# dualpowersupply.net
KiCad netlist of a schematic drawn in EAGLE
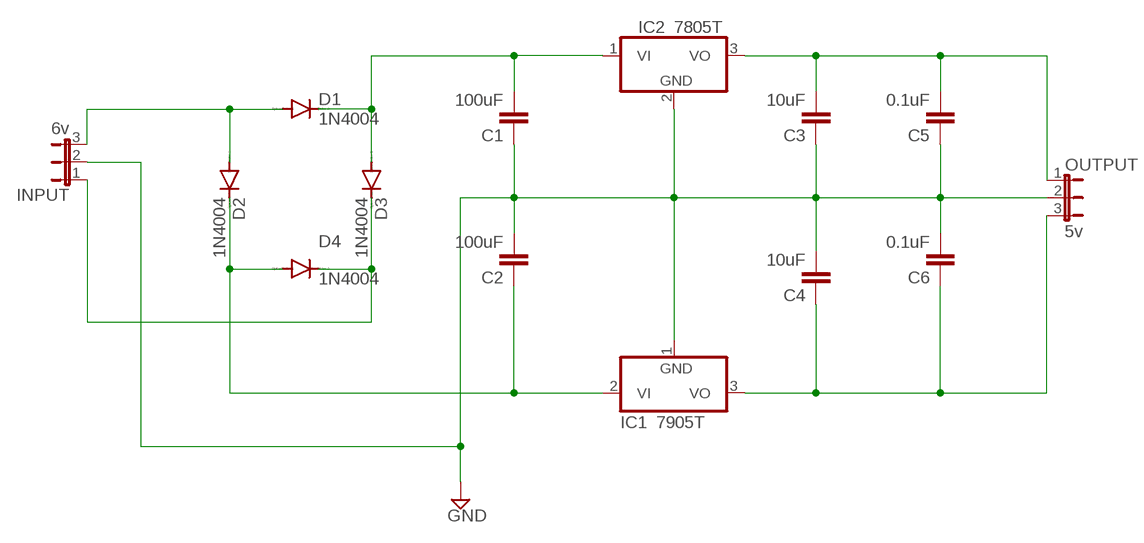
[diagram p0: schematic, sheet 1]

(export (version "E")
  (design (tool "Eeschema 10.0.6"))
  (components
    (comp (ref "C1")
      (value "100uF")
      (footprint "eagle-import:C2.5-2")
      (libsource (lib "eagle-import") (part "C2.5/2"))
    )
    (comp (ref "C2")
      (value "100uF")
      (footprint "eagle-import:C2.5-2")
      (libsource (lib "eagle-import") (part "C2.5/2"))
    )
    (comp (ref "C3")
      (value "10uF")
      (footprint "eagle-import:C2.5-2")
      (libsource (lib "eagle-import") (part "C2.5/2"))
    )
    (comp (ref "C4")
      (value "10uF")
      (footprint "eagle-import:C2.5-2")
      (libsource (lib "eagle-import") (part "C2.5/2"))
    )
    (comp (ref "C5")
      (value "0.1uF")
      (footprint "eagle-import:C2.5-2")
      (libsource (lib "eagle-import") (part "C2.5/2"))
    )
    (comp (ref "C6")
      (value "0.1uF")
      (footprint "eagle-import:C2.5-2")
      (libsource (lib "eagle-import") (part "C2.5/2"))
    )
    (comp (ref "D1")
      (value "1N4004")
      (footprint "eagle-import:DO41-10")
      (libsource (lib "eagle-import") (part "1N4004"))
    )
    (comp (ref "D2")
      (value "1N4004")
      (footprint "eagle-import:DO41-10")
      (libsource (lib "eagle-import") (part "1N4004"))
    )
    (comp (ref "D3")
      (value "1N4004")
      (footprint "eagle-import:DO41-10")
      (libsource (lib "eagle-import") (part "1N4004"))
    )
    (comp (ref "D4")
      (value "1N4004")
      (footprint "eagle-import:DO41-10")
      (libsource (lib "eagle-import") (part "1N4004"))
    )
    (comp (ref "IC1")
      (value "7905T")
      (footprint "eagle-import:TO220H")
      (libsource (lib "eagle-import") (part "79T08"))
    )
    (comp (ref "IC2")
      (value "7805T")
      (footprint "eagle-import:TO220H")
      (libsource (lib "eagle-import") (part "78T05"))
    )
    (comp (ref "INPUT")
      (value "6v")
      (footprint "eagle-import:JP2")
      (libsource (lib "eagle-import") (part "JP2E"))
    )
    (comp (ref "OUTPUT")
      (value "5v")
      (footprint "eagle-import:JP2")
      (libsource (lib "eagle-import") (part "JP2E"))
    )
  )
  (nets
    (net (code "1") (name "GND") (class "Default")
      (node (ref "C1") (pin "1") (pinfunction "1_1") (pintype "passive"))
      (node (ref "C2") (pin "2") (pinfunction "2_2") (pintype "passive"))
      (node (ref "C3") (pin "1") (pinfunction "1_1") (pintype "passive"))
      (node (ref "C4") (pin "2") (pinfunction "2_2") (pintype "passive"))
      (node (ref "C5") (pin "1") (pinfunction "1_1") (pintype "passive"))
      (node (ref "C6") (pin "2") (pinfunction "2_2") (pintype "passive"))
      (node (ref "IC1") (pin "1") (pinfunction "GND_1") (pintype "passive"))
      (node (ref "IC2") (pin "2") (pinfunction "GND_2") (pintype "passive"))
      (node (ref "INPUT") (pin "2") (pinfunction "2_2") (pintype "passive"))
      (node (ref "OUTPUT") (pin "2") (pinfunction "2_2") (pintype "passive"))
    )
    (net (code "2") (name "Net-(D1-PadA)") (class "Default")
      (node (ref "D1") (pin "A") (pinfunction "A_A") (pintype "passive"))
      (node (ref "D2") (pin "A") (pinfunction "A_A") (pintype "passive"))
      (node (ref "INPUT") (pin "3") (pinfunction "3_3") (pintype "passive"))
    )
    (net (code "3") (name "Net-(D3-PadC)") (class "Default")
      (node (ref "D3") (pin "C") (pinfunction "C_C") (pintype "passive"))
      (node (ref "D4") (pin "C") (pinfunction "C_C") (pintype "passive"))
      (node (ref "INPUT") (pin "1") (pinfunction "1_1") (pintype "passive"))
    )
    (net (code "4") (name "Net-(IC1-VI)") (class "Default")
      (node (ref "C2") (pin "1") (pinfunction "1_1") (pintype "passive"))
      (node (ref "D2") (pin "C") (pinfunction "C_C") (pintype "passive"))
      (node (ref "D4") (pin "A") (pinfunction "A_A") (pintype "passive"))
      (node (ref "IC1") (pin "2") (pinfunction "VI_2") (pintype "input"))
    )
    (net (code "5") (name "Net-(IC1-VO)") (class "Default")
      (node (ref "C4") (pin "1") (pinfunction "1_1") (pintype "passive"))
      (node (ref "C6") (pin "1") (pinfunction "1_1") (pintype "passive"))
      (node (ref "IC1") (pin "3") (pinfunction "VO_3") (pintype "passive"))
      (node (ref "OUTPUT") (pin "3") (pinfunction "3_3") (pintype "passive"))
    )
    (net (code "6") (name "Net-(IC2-VI)") (class "Default")
      (node (ref "C1") (pin "2") (pinfunction "2_2") (pintype "passive"))
      (node (ref "D1") (pin "C") (pinfunction "C_C") (pintype "passive"))
      (node (ref "D3") (pin "A") (pinfunction "A_A") (pintype "passive"))
      (node (ref "IC2") (pin "1") (pinfunction "VI_1") (pintype "input"))
    )
    (net (code "7") (name "Net-(IC2-VO)") (class "Default")
      (node (ref "C3") (pin "2") (pinfunction "2_2") (pintype "passive"))
      (node (ref "C5") (pin "2") (pinfunction "2_2") (pintype "passive"))
      (node (ref "IC2") (pin "3") (pinfunction "VO_3") (pintype "passive"))
      (node (ref "OUTPUT") (pin "1") (pinfunction "1_1") (pintype "passive"))
    )
  )
)
